# J2.net
KiCad netlist of a schematic drawn in Altium Designer
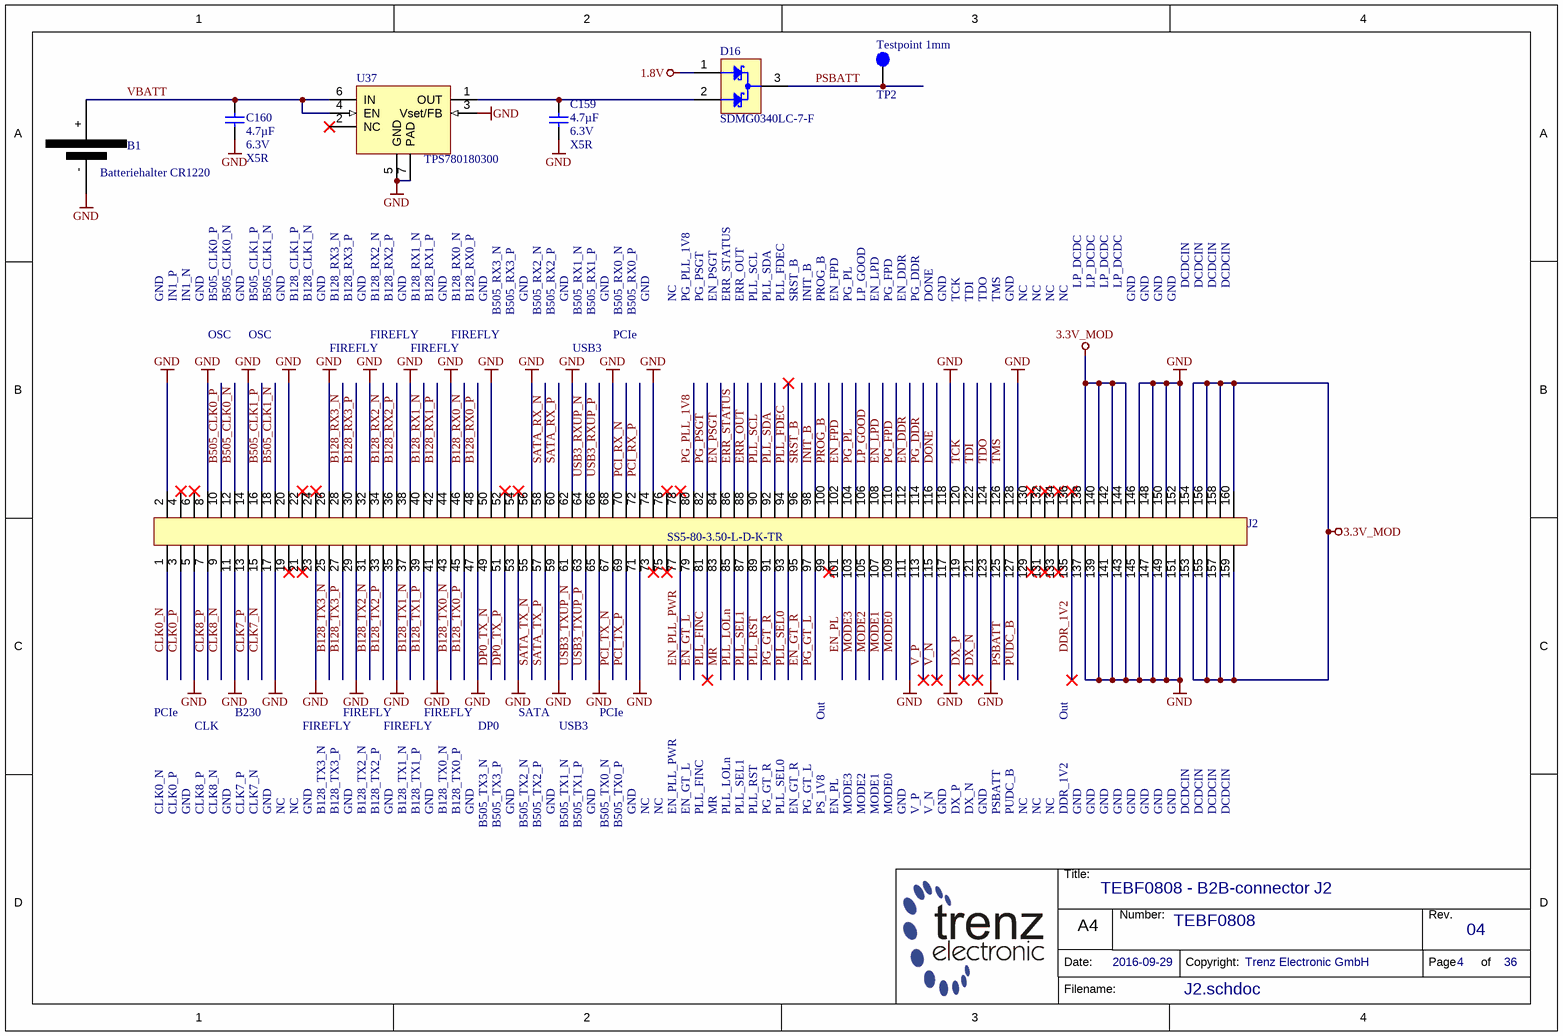
[diagram p0: J2.schdoc]

(export (version "E")
  (design (tool "Eeschema 10.0.6"))
  (components
    (comp (ref "B1")
      (value "Batteriehalter CR1220")
      (footprint "CR1220")
      (libsource (lib "TE") (part "BH1060"))
    )
    (comp (ref "C159")
      (value "4.7µF")
      (footprint "CAPC1005X60N")
      (description "KON 4.7µF 6.3V X5R SMD 20%")
      (fields
        (field (name "VOLTAGE") "6.3V")
        (field (name "TECHNOLOGY") "X5R")
        (field (name "TOLERANCE") "20%")
      )
      (libsource (lib "TE") (part "CAP-NP"))
    )
    (comp (ref "C160")
      (value "4.7µF")
      (footprint "CAPC1005X60N")
      (description "KON 4.7µF 6.3V X5R SMD 20%")
      (fields
        (field (name "VOLTAGE") "6.3V")
        (field (name "TECHNOLOGY") "X5R")
        (field (name "TOLERANCE") "20%")
      )
      (libsource (lib "TE") (part "CAP-NP"))
    )
    (comp (ref "D16")
      (value "SDMG0340LC-7-F")
      (footprint "SOT65P210X110-3N")
      (libsource (lib "TE") (part "SDMG0340LC"))
    )
    (comp (ref "J2")
      (value "SS5-80-3.50-L-D-K-TR")
      (footprint "SS5-80-3.50-L-D-K-TR")
      (description "Samtec Ultra Fine Pitch Socket REF192552-01, 160 Pins")
      (libsource (lib "TE") (part "CON-160"))
    )
    (comp (ref "TP2") (value "Testpoint 1mm") (footprint "TP_1mm") (libsource (lib "TE") (part "TP")))
    (comp (ref "U37")
      (value "TPS780180300")
      (footprint "SON65P200X200X80-7N")
      (libsource (lib "TE") (part "TPS780DRV"))
    )
  )
  (nets
    (net (code "1") (name "/B128_RX0_N") (class "Default")
      (node (ref "J2") (pin "46") (pinfunction "46_46") (pintype "passive"))
    )
    (net (code "2") (name "/B128_RX0_P") (class "Default")
      (node (ref "J2") (pin "48") (pinfunction "48_48") (pintype "passive"))
    )
    (net (code "3") (name "/B128_RX1_N") (class "Default")
      (node (ref "J2") (pin "40") (pinfunction "40_40") (pintype "passive"))
    )
    (net (code "4") (name "/B128_RX1_P") (class "Default")
      (node (ref "J2") (pin "42") (pinfunction "42_42") (pintype "passive"))
    )
    (net (code "5") (name "/B128_RX2_N") (class "Default")
      (node (ref "J2") (pin "34") (pinfunction "34_34") (pintype "passive"))
    )
    (net (code "6") (name "/B128_RX2_P") (class "Default")
      (node (ref "J2") (pin "36") (pinfunction "36_36") (pintype "passive"))
    )
    (net (code "7") (name "/B128_RX3_N") (class "Default")
      (node (ref "J2") (pin "28") (pinfunction "28_28") (pintype "passive"))
    )
    (net (code "8") (name "/B128_RX3_P") (class "Default")
      (node (ref "J2") (pin "30") (pinfunction "30_30") (pintype "passive"))
    )
    (net (code "9") (name "/B128_TX0_N") (class "Default")
      (node (ref "J2") (pin "43") (pinfunction "43_43") (pintype "passive"))
    )
    (net (code "10") (name "/B128_TX0_P") (class "Default")
      (node (ref "J2") (pin "45") (pinfunction "45_45") (pintype "passive"))
    )
    (net (code "11") (name "/B128_TX1_N") (class "Default")
      (node (ref "J2") (pin "37") (pinfunction "37_37") (pintype "passive"))
    )
    (net (code "12") (name "/B128_TX1_P") (class "Default")
      (node (ref "J2") (pin "39") (pinfunction "39_39") (pintype "passive"))
    )
    (net (code "13") (name "/B128_TX2_N") (class "Default")
      (node (ref "J2") (pin "31") (pinfunction "31_31") (pintype "passive"))
    )
    (net (code "14") (name "/B128_TX2_P") (class "Default")
      (node (ref "J2") (pin "33") (pinfunction "33_33") (pintype "passive"))
    )
    (net (code "15") (name "/B128_TX3_N") (class "Default")
      (node (ref "J2") (pin "25") (pinfunction "25_25") (pintype "passive"))
    )
    (net (code "16") (name "/B128_TX3_P") (class "Default")
      (node (ref "J2") (pin "27") (pinfunction "27_27") (pintype "passive"))
    )
    (net (code "17") (name "/B505_CLK0_N") (class "Default")
      (node (ref "J2") (pin "12") (pinfunction "12_12") (pintype "passive"))
    )
    (net (code "18") (name "/B505_CLK0_P") (class "Default")
      (node (ref "J2") (pin "10") (pinfunction "10_10") (pintype "passive"))
    )
    (net (code "19") (name "/B505_CLK1_N") (class "Default")
      (node (ref "J2") (pin "18") (pinfunction "18_18") (pintype "passive"))
    )
    (net (code "20") (name "/B505_CLK1_P") (class "Default")
      (node (ref "J2") (pin "16") (pinfunction "16_16") (pintype "passive"))
    )
    (net (code "21") (name "/CLK0_N") (class "Default")
      (node (ref "J2") (pin "1") (pinfunction "1_1") (pintype "passive"))
    )
    (net (code "22") (name "/CLK0_P") (class "Default")
      (node (ref "J2") (pin "3") (pinfunction "3_3") (pintype "passive"))
    )
    (net (code "23") (name "/CLK7_N") (class "Default")
      (node (ref "J2") (pin "15") (pinfunction "15_15") (pintype "passive"))
    )
    (net (code "24") (name "/CLK7_P") (class "Default")
      (node (ref "J2") (pin "13") (pinfunction "13_13") (pintype "passive"))
    )
    (net (code "25") (name "/CLK8_N") (class "Default")
      (node (ref "J2") (pin "9") (pinfunction "9_9") (pintype "passive"))
    )
    (net (code "26") (name "/CLK8_P") (class "Default")
      (node (ref "J2") (pin "7") (pinfunction "7_7") (pintype "passive"))
    )
    (net (code "27") (name "/DDR_1V2") (class "Default")
      (node (ref "J2") (pin "135") (pinfunction "135_135") (pintype "passive+no_connect"))
    )
    (net (code "28") (name "/DONE") (class "Default")
      (node (ref "J2") (pin "116") (pinfunction "116_116") (pintype "passive"))
    )
    (net (code "29") (name "/DP0_TX_N") (class "Default")
      (node (ref "J2") (pin "49") (pinfunction "49_49") (pintype "passive"))
    )
    (net (code "30") (name "/DP0_TX_P") (class "Default")
      (node (ref "J2") (pin "51") (pinfunction "51_51") (pintype "passive"))
    )
    (net (code "31") (name "/DX_N") (class "Default")
      (node (ref "J2") (pin "121") (pinfunction "121_121") (pintype "passive+no_connect"))
    )
    (net (code "32") (name "/DX_P") (class "Default")
      (node (ref "J2") (pin "119") (pinfunction "119_119") (pintype "passive+no_connect"))
    )
    (net (code "33") (name "/EN_DDR") (class "Default")
      (node (ref "J2") (pin "112") (pinfunction "112_112") (pintype "passive"))
    )
    (net (code "34") (name "/EN_FPD") (class "Default")
      (node (ref "J2") (pin "102") (pinfunction "102_102") (pintype "passive"))
    )
    (net (code "35") (name "/EN_GT_L") (class "Default")
      (node (ref "J2") (pin "79") (pinfunction "79_79") (pintype "passive"))
    )
    (net (code "36") (name "/EN_GT_R") (class "Default")
      (node (ref "J2") (pin "95") (pinfunction "95_95") (pintype "passive"))
    )
    (net (code "37") (name "/EN_LPD") (class "Default")
      (node (ref "J2") (pin "108") (pinfunction "108_108") (pintype "passive"))
    )
    (net (code "38") (name "/EN_PL") (class "Default")
      (node (ref "J2") (pin "101") (pinfunction "101_101") (pintype "passive"))
    )
    (net (code "39") (name "/EN_PLL_PWR") (class "Default")
      (node (ref "J2") (pin "77") (pinfunction "77_77") (pintype "passive"))
    )
    (net (code "40") (name "/EN_PSGT") (class "Default")
      (node (ref "J2") (pin "84") (pinfunction "84_84") (pintype "passive"))
    )
    (net (code "41") (name "/ERR_OUT") (class "Default")
      (node (ref "J2") (pin "88") (pinfunction "88_88") (pintype "passive"))
    )
    (net (code "42") (name "/ERR_STATUS") (class "Default")
      (node (ref "J2") (pin "86") (pinfunction "86_86") (pintype "passive"))
    )
    (net (code "43") (name "/INIT_B") (class "Default")
      (node (ref "J2") (pin "98") (pinfunction "98_98") (pintype "passive"))
    )
    (net (code "44") (name "/LP_GOOD") (class "Default")
      (node (ref "J2") (pin "106") (pinfunction "106_106") (pintype "passive"))
    )
    (net (code "45") (name "/MODE0") (class "Default")
      (node (ref "J2") (pin "109") (pinfunction "109_109") (pintype "passive"))
    )
    (net (code "46") (name "/MODE1") (class "Default")
      (node (ref "J2") (pin "107") (pinfunction "107_107") (pintype "passive"))
    )
    (net (code "47") (name "/MODE2") (class "Default")
      (node (ref "J2") (pin "105") (pinfunction "105_105") (pintype "passive"))
    )
    (net (code "48") (name "/MODE3") (class "Default")
      (node (ref "J2") (pin "103") (pinfunction "103_103") (pintype "passive"))
    )
    (net (code "49") (name "/MR") (class "Default")
      (node (ref "J2") (pin "83") (pinfunction "83_83") (pintype "passive"))
    )
    (net (code "50") (name "/PCI_RX_N") (class "Default")
      (node (ref "J2") (pin "70") (pinfunction "70_70") (pintype "passive"))
    )
    (net (code "51") (name "/PCI_RX_P") (class "Default")
      (node (ref "J2") (pin "72") (pinfunction "72_72") (pintype "passive"))
    )
    (net (code "52") (name "/PCI_TX_N") (class "Default")
      (node (ref "J2") (pin "67") (pinfunction "67_67") (pintype "passive"))
    )
    (net (code "53") (name "/PCI_TX_P") (class "Default")
      (node (ref "J2") (pin "69") (pinfunction "69_69") (pintype "passive"))
    )
    (net (code "54") (name "/PG_DDR") (class "Default")
      (node (ref "J2") (pin "114") (pinfunction "114_114") (pintype "passive"))
    )
    (net (code "55") (name "/PG_FPD") (class "Default")
      (node (ref "J2") (pin "110") (pinfunction "110_110") (pintype "passive"))
    )
    (net (code "56") (name "/PG_GT_L") (class "Default")
      (node (ref "J2") (pin "97") (pinfunction "97_97") (pintype "passive"))
    )
    (net (code "57") (name "/PG_GT_R") (class "Default")
      (node (ref "J2") (pin "91") (pinfunction "91_91") (pintype "passive"))
    )
    (net (code "58") (name "/PG_PL") (class "Default")
      (node (ref "J2") (pin "104") (pinfunction "104_104") (pintype "passive"))
    )
    (net (code "59") (name "/PG_PLL_1V8") (class "Default")
      (node (ref "J2") (pin "80") (pinfunction "80_80") (pintype "passive"))
    )
    (net (code "60") (name "/PG_PSGT") (class "Default")
      (node (ref "J2") (pin "82") (pinfunction "82_82") (pintype "passive"))
    )
    (net (code "61") (name "/PLL_FDEC") (class "Default")
      (node (ref "J2") (pin "94") (pinfunction "94_94") (pintype "passive+no_connect"))
    )
    (net (code "62") (name "/PLL_FINC") (class "Default")
      (node (ref "J2") (pin "81") (pinfunction "81_81") (pintype "passive+no_connect"))
    )
    (net (code "63") (name "/PLL_LOLn") (class "Default")
      (node (ref "J2") (pin "85") (pinfunction "85_85") (pintype "passive"))
    )
    (net (code "64") (name "/PLL_RST") (class "Default")
      (node (ref "J2") (pin "89") (pinfunction "89_89") (pintype "passive"))
    )
    (net (code "65") (name "/PLL_SCL") (class "Default")
      (node (ref "J2") (pin "90") (pinfunction "90_90") (pintype "passive"))
    )
    (net (code "66") (name "/PLL_SDA") (class "Default")
      (node (ref "J2") (pin "92") (pinfunction "92_92") (pintype "passive"))
    )
    (net (code "67") (name "/PLL_SEL0") (class "Default")
      (node (ref "J2") (pin "93") (pinfunction "93_93") (pintype "passive"))
    )
    (net (code "68") (name "/PLL_SEL1") (class "Default")
      (node (ref "J2") (pin "87") (pinfunction "87_87") (pintype "passive"))
    )
    (net (code "69") (name "/PROG_B") (class "Default")
      (node (ref "J2") (pin "100") (pinfunction "100_100") (pintype "passive"))
    )
    (net (code "70") (name "/PSBATT") (class "Default")
      (node (ref "D16") (pin "3") (pinfunction "K_3") (pintype "passive"))
      (node (ref "J2") (pin "125") (pinfunction "125_125") (pintype "passive"))
      (node (ref "TP2") (pin "1") (pintype "passive"))
    )
    (net (code "71") (name "/PUDC_B") (class "Default")
      (node (ref "J2") (pin "127") (pinfunction "127_127") (pintype "passive"))
    )
    (net (code "72") (name "/SATA_RX_N") (class "Default")
      (node (ref "J2") (pin "58") (pinfunction "58_58") (pintype "passive"))
    )
    (net (code "73") (name "/SATA_RX_P") (class "Default")
      (node (ref "J2") (pin "60") (pinfunction "60_60") (pintype "passive"))
    )
    (net (code "74") (name "/SATA_TX_N") (class "Default")
      (node (ref "J2") (pin "55") (pinfunction "55_55") (pintype "passive"))
    )
    (net (code "75") (name "/SATA_TX_P") (class "Default")
      (node (ref "J2") (pin "57") (pinfunction "57_57") (pintype "passive"))
    )
    (net (code "76") (name "/SRST_B") (class "Default")
      (node (ref "J2") (pin "96") (pinfunction "96_96") (pintype "passive"))
    )
    (net (code "77") (name "/TCK") (class "Default")
      (node (ref "J2") (pin "120") (pinfunction "120_120") (pintype "passive"))
    )
    (net (code "78") (name "/TDI") (class "Default")
      (node (ref "J2") (pin "122") (pinfunction "122_122") (pintype "passive"))
    )
    (net (code "79") (name "/TDO") (class "Default")
      (node (ref "J2") (pin "124") (pinfunction "124_124") (pintype "passive"))
    )
    (net (code "80") (name "/TMS") (class "Default")
      (node (ref "J2") (pin "126") (pinfunction "126_126") (pintype "passive"))
    )
    (net (code "81") (name "/USB3_RXUP_N") (class "Default")
      (node (ref "J2") (pin "64") (pinfunction "64_64") (pintype "passive"))
    )
    (net (code "82") (name "/USB3_RXUP_P") (class "Default")
      (node (ref "J2") (pin "66") (pinfunction "66_66") (pintype "passive"))
    )
    (net (code "83") (name "/USB3_TXUP_N") (class "Default")
      (node (ref "J2") (pin "61") (pinfunction "61_61") (pintype "passive"))
    )
    (net (code "84") (name "/USB3_TXUP_P") (class "Default")
      (node (ref "J2") (pin "63") (pinfunction "63_63") (pintype "passive"))
    )
    (net (code "85") (name "/VBATT") (class "Default")
      (node (ref "B1") (pin "+") (pinfunction "+_+") (pintype "power_in"))
      (node (ref "C160") (pin "1") (pinfunction "1_1") (pintype "passive"))
      (node (ref "U37") (pin "4") (pinfunction "EN_4") (pintype "input"))
      (node (ref "U37") (pin "6") (pinfunction "IN_6") (pintype "power_in"))
    )
    (net (code "86") (name "/V_N") (class "Default")
      (node (ref "J2") (pin "115") (pinfunction "115_115") (pintype "passive+no_connect"))
    )
    (net (code "87") (name "/V_P") (class "Default")
      (node (ref "J2") (pin "113") (pinfunction "113_113") (pintype "passive+no_connect"))
    )
    (net (code "88") (name "1.8V") (class "Default")
      (node (ref "D16") (pin "1") (pinfunction "A_1") (pintype "passive"))
    )
    (net (code "89") (name "3.3V_MOD") (class "Default")
      (node (ref "J2") (pin "138") (pinfunction "138_138") (pintype "passive"))
      (node (ref "J2") (pin "140") (pinfunction "140_140") (pintype "passive"))
      (node (ref "J2") (pin "142") (pinfunction "142_142") (pintype "passive"))
      (node (ref "J2") (pin "144") (pinfunction "144_144") (pintype "passive"))
      (node (ref "J2") (pin "153") (pinfunction "153_153") (pintype "passive"))
      (node (ref "J2") (pin "154") (pinfunction "154_154") (pintype "passive"))
      (node (ref "J2") (pin "155") (pinfunction "155_155") (pintype "passive"))
      (node (ref "J2") (pin "156") (pinfunction "156_156") (pintype "passive"))
      (node (ref "J2") (pin "157") (pinfunction "157_157") (pintype "passive"))
      (node (ref "J2") (pin "158") (pinfunction "158_158") (pintype "passive"))
      (node (ref "J2") (pin "159") (pinfunction "159_159") (pintype "passive"))
      (node (ref "J2") (pin "160") (pinfunction "160_160") (pintype "passive"))
    )
    (net (code "90") (name "GND") (class "Default")
      (node (ref "B1") (pin "-") (pinfunction "-_-") (pintype "power_in"))
      (node (ref "C159") (pin "2") (pinfunction "2_2") (pintype "passive"))
      (node (ref "C160") (pin "2") (pinfunction "2_2") (pintype "passive"))
      (node (ref "J2") (pin "11") (pinfunction "11_11") (pintype "passive"))
      (node (ref "J2") (pin "111") (pinfunction "111_111") (pintype "passive"))
      (node (ref "J2") (pin "117") (pinfunction "117_117") (pintype "passive"))
      (node (ref "J2") (pin "118") (pinfunction "118_118") (pintype "passive"))
      (node (ref "J2") (pin "123") (pinfunction "123_123") (pintype "passive"))
      (node (ref "J2") (pin "128") (pinfunction "128_128") (pintype "passive"))
      (node (ref "J2") (pin "137") (pinfunction "137_137") (pintype "passive"))
      (node (ref "J2") (pin "139") (pinfunction "139_139") (pintype "passive"))
      (node (ref "J2") (pin "14") (pinfunction "14_14") (pintype "passive"))
      (node (ref "J2") (pin "141") (pinfunction "141_141") (pintype "passive"))
      (node (ref "J2") (pin "143") (pinfunction "143_143") (pintype "passive"))
      (node (ref "J2") (pin "145") (pinfunction "145_145") (pintype "passive"))
      (node (ref "J2") (pin "146") (pinfunction "146_146") (pintype "passive"))
      (node (ref "J2") (pin "147") (pinfunction "147_147") (pintype "passive"))
      (node (ref "J2") (pin "148") (pinfunction "148_148") (pintype "passive"))
      (node (ref "J2") (pin "149") (pinfunction "149_149") (pintype "passive"))
      (node (ref "J2") (pin "150") (pinfunction "150_150") (pintype "passive"))
      (node (ref "J2") (pin "151") (pinfunction "151_151") (pintype "passive"))
      (node (ref "J2") (pin "152") (pinfunction "152_152") (pintype "passive"))
      (node (ref "J2") (pin "17") (pinfunction "17_17") (pintype "passive"))
      (node (ref "J2") (pin "2") (pinfunction "2_2") (pintype "passive"))
      (node (ref "J2") (pin "20") (pinfunction "20_20") (pintype "passive"))
      (node (ref "J2") (pin "23") (pinfunction "23_23") (pintype "passive"))
      (node (ref "J2") (pin "26") (pinfunction "26_26") (pintype "passive"))
      (node (ref "J2") (pin "29") (pinfunction "29_29") (pintype "passive"))
      (node (ref "J2") (pin "32") (pinfunction "32_32") (pintype "passive"))
      (node (ref "J2") (pin "35") (pinfunction "35_35") (pintype "passive"))
      (node (ref "J2") (pin "38") (pinfunction "38_38") (pintype "passive"))
      (node (ref "J2") (pin "41") (pinfunction "41_41") (pintype "passive"))
      (node (ref "J2") (pin "44") (pinfunction "44_44") (pintype "passive"))
      (node (ref "J2") (pin "47") (pinfunction "47_47") (pintype "passive"))
      (node (ref "J2") (pin "5") (pinfunction "5_5") (pintype "passive"))
      (node (ref "J2") (pin "50") (pinfunction "50_50") (pintype "passive"))
      (node (ref "J2") (pin "53") (pinfunction "53_53") (pintype "passive"))
      (node (ref "J2") (pin "56") (pinfunction "56_56") (pintype "passive"))
      (node (ref "J2") (pin "59") (pinfunction "59_59") (pintype "passive"))
      (node (ref "J2") (pin "62") (pinfunction "62_62") (pintype "passive"))
      (node (ref "J2") (pin "65") (pinfunction "65_65") (pintype "passive"))
      (node (ref "J2") (pin "68") (pinfunction "68_68") (pintype "passive"))
      (node (ref "J2") (pin "71") (pinfunction "71_71") (pintype "passive"))
      (node (ref "J2") (pin "74") (pinfunction "74_74") (pintype "passive"))
      (node (ref "J2") (pin "8") (pinfunction "8_8") (pintype "passive"))
      (node (ref "U37") (pin "3") (pinfunction "Vset/FB_3") (pintype "input"))
      (node (ref "U37") (pin "5") (pinfunction "GND_5") (pintype "power_in"))
      (node (ref "U37") (pin "7") (pinfunction "PAD_7") (pintype "passive"))
    )
    (net (code "91") (name "Net-(U37-OUT)") (class "Default")
      (node (ref "C159") (pin "1") (pinfunction "1_1") (pintype "passive"))
      (node (ref "D16") (pin "2") (pinfunction "A_2") (pintype "passive"))
      (node (ref "U37") (pin "1") (pinfunction "OUT_1") (pintype "passive"))
    )
    (net (code "92") (name "unconnected-(J2-Pad4)") (class "Default")
      (node (ref "J2") (pin "4") (pinfunction "4_4") (pintype "passive+no_connect"))
    )
    (net (code "93") (name "unconnected-(J2-Pad6)") (class "Default")
      (node (ref "J2") (pin "6") (pinfunction "6_6") (pintype "passive+no_connect"))
    )
    (net (code "94") (name "unconnected-(J2-Pad19)") (class "Default")
      (node (ref "J2") (pin "19") (pinfunction "19_19") (pintype "passive+no_connect"))
    )
    (net (code "95") (name "unconnected-(J2-Pad21)") (class "Default")
      (node (ref "J2") (pin "21") (pinfunction "21_21") (pintype "passive+no_connect"))
    )
    (net (code "96") (name "unconnected-(J2-Pad22)") (class "Default")
      (node (ref "J2") (pin "22") (pinfunction "22_22") (pintype "passive+no_connect"))
    )
    (net (code "97") (name "unconnected-(J2-Pad24)") (class "Default")
      (node (ref "J2") (pin "24") (pinfunction "24_24") (pintype "passive+no_connect"))
    )
    (net (code "98") (name "unconnected-(J2-Pad52)") (class "Default")
      (node (ref "J2") (pin "52") (pinfunction "52_52") (pintype "passive+no_connect"))
    )
    (net (code "99") (name "unconnected-(J2-Pad54)") (class "Default")
      (node (ref "J2") (pin "54") (pinfunction "54_54") (pintype "passive+no_connect"))
    )
    (net (code "100") (name "unconnected-(J2-Pad73)") (class "Default")
      (node (ref "J2") (pin "73") (pinfunction "73_73") (pintype "passive+no_connect"))
    )
    (net (code "101") (name "unconnected-(J2-Pad75)") (class "Default")
      (node (ref "J2") (pin "75") (pinfunction "75_75") (pintype "passive+no_connect"))
    )
    (net (code "102") (name "unconnected-(J2-Pad76)") (class "Default")
      (node (ref "J2") (pin "76") (pinfunction "76_76") (pintype "passive+no_connect"))
    )
    (net (code "103") (name "unconnected-(J2-Pad78)") (class "Default")
      (node (ref "J2") (pin "78") (pinfunction "78_78") (pintype "passive+no_connect"))
    )
    (net (code "104") (name "unconnected-(J2-Pad99)") (class "Default")
      (node (ref "J2") (pin "99") (pinfunction "99_99") (pintype "passive+no_connect"))
    )
    (net (code "105") (name "unconnected-(J2-Pad129)") (class "Default")
      (node (ref "J2") (pin "129") (pinfunction "129_129") (pintype "passive+no_connect"))
    )
    (net (code "106") (name "unconnected-(J2-Pad130)") (class "Default")
      (node (ref "J2") (pin "130") (pinfunction "130_130") (pintype "passive+no_connect"))
    )
    (net (code "107") (name "unconnected-(J2-Pad131)") (class "Default")
      (node (ref "J2") (pin "131") (pinfunction "131_131") (pintype "passive+no_connect"))
    )
    (net (code "108") (name "unconnected-(J2-Pad132)") (class "Default")
      (node (ref "J2") (pin "132") (pinfunction "132_132") (pintype "passive+no_connect"))
    )
    (net (code "109") (name "unconnected-(J2-Pad133)") (class "Default")
      (node (ref "J2") (pin "133") (pinfunction "133_133") (pintype "passive+no_connect"))
    )
    (net (code "110") (name "unconnected-(J2-Pad134)") (class "Default")
      (node (ref "J2") (pin "134") (pinfunction "134_134") (pintype "passive+no_connect"))
    )
    (net (code "111") (name "unconnected-(J2-Pad136)") (class "Default")
      (node (ref "J2") (pin "136") (pinfunction "136_136") (pintype "passive+no_connect"))
    )
    (net (code "112") (name "unconnected-(U37-NC-Pad2)") (class "Default")
      (node (ref "U37") (pin "2") (pinfunction "NC_2") (pintype "passive+no_connect"))
    )
  )
)
